# Cheer_Dev_Kit.net
KiCad netlist of a schematic drawn in EAGLE
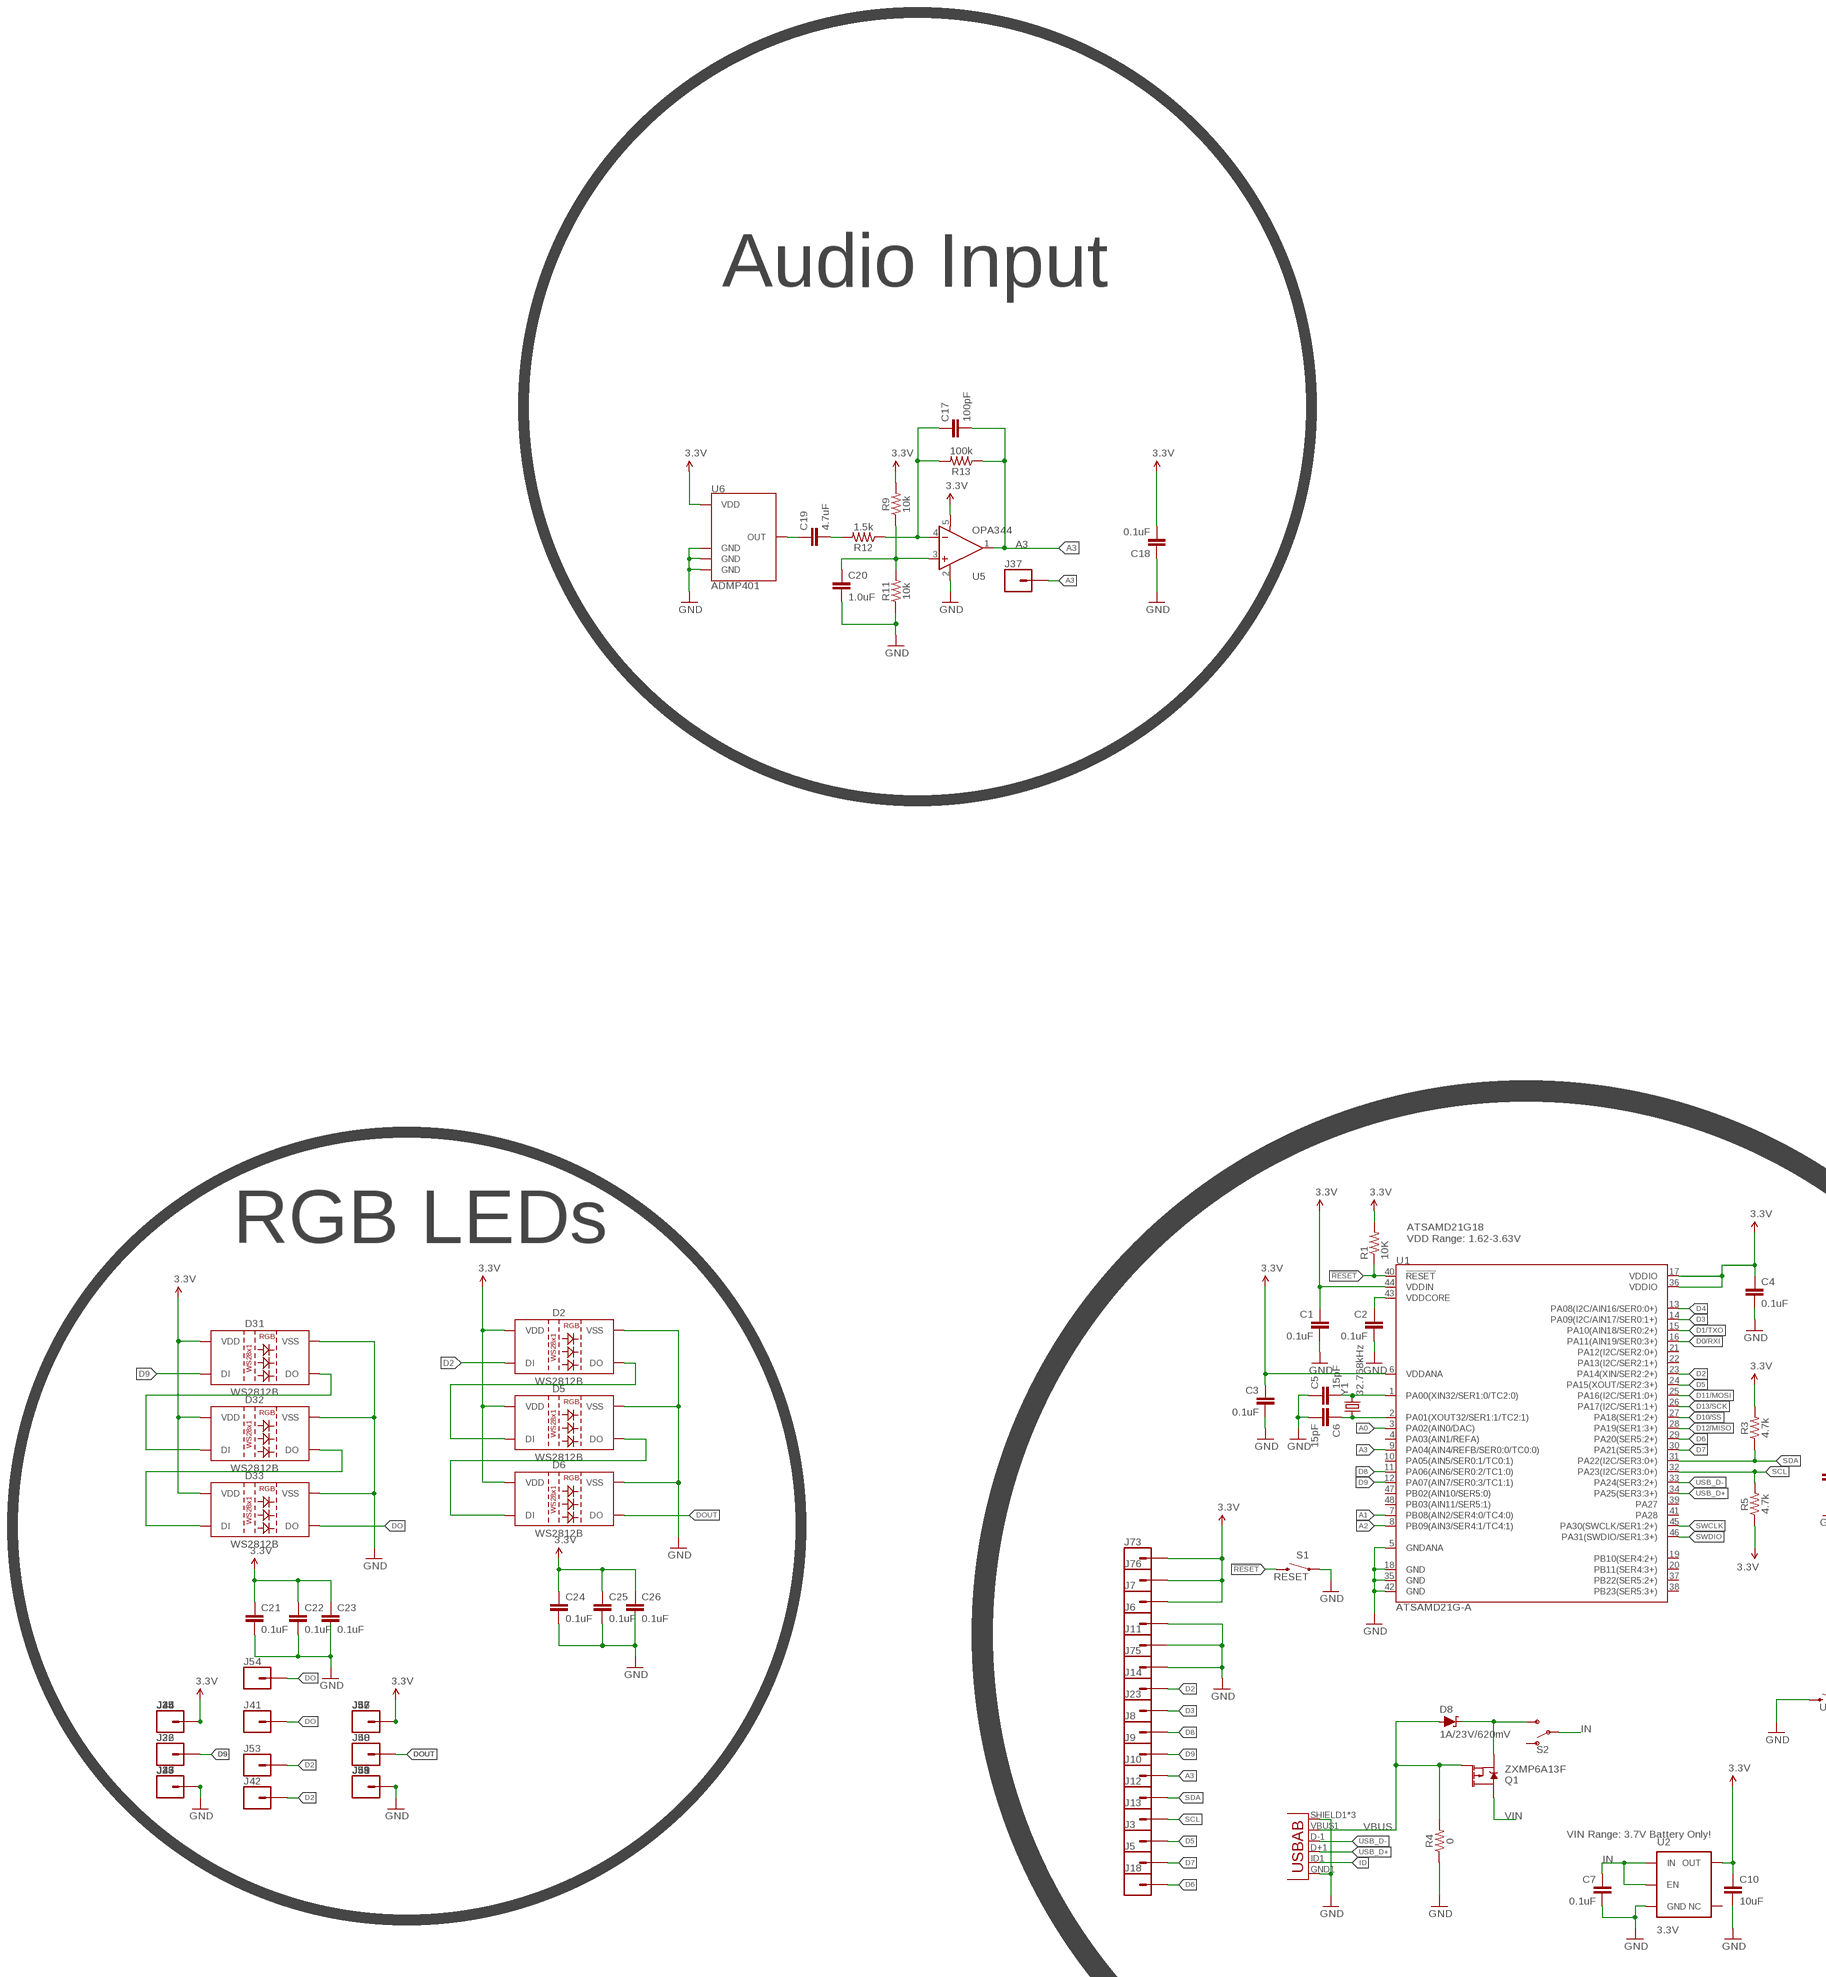
[diagram p0: schematic, sheet 1, part 1 of 3]
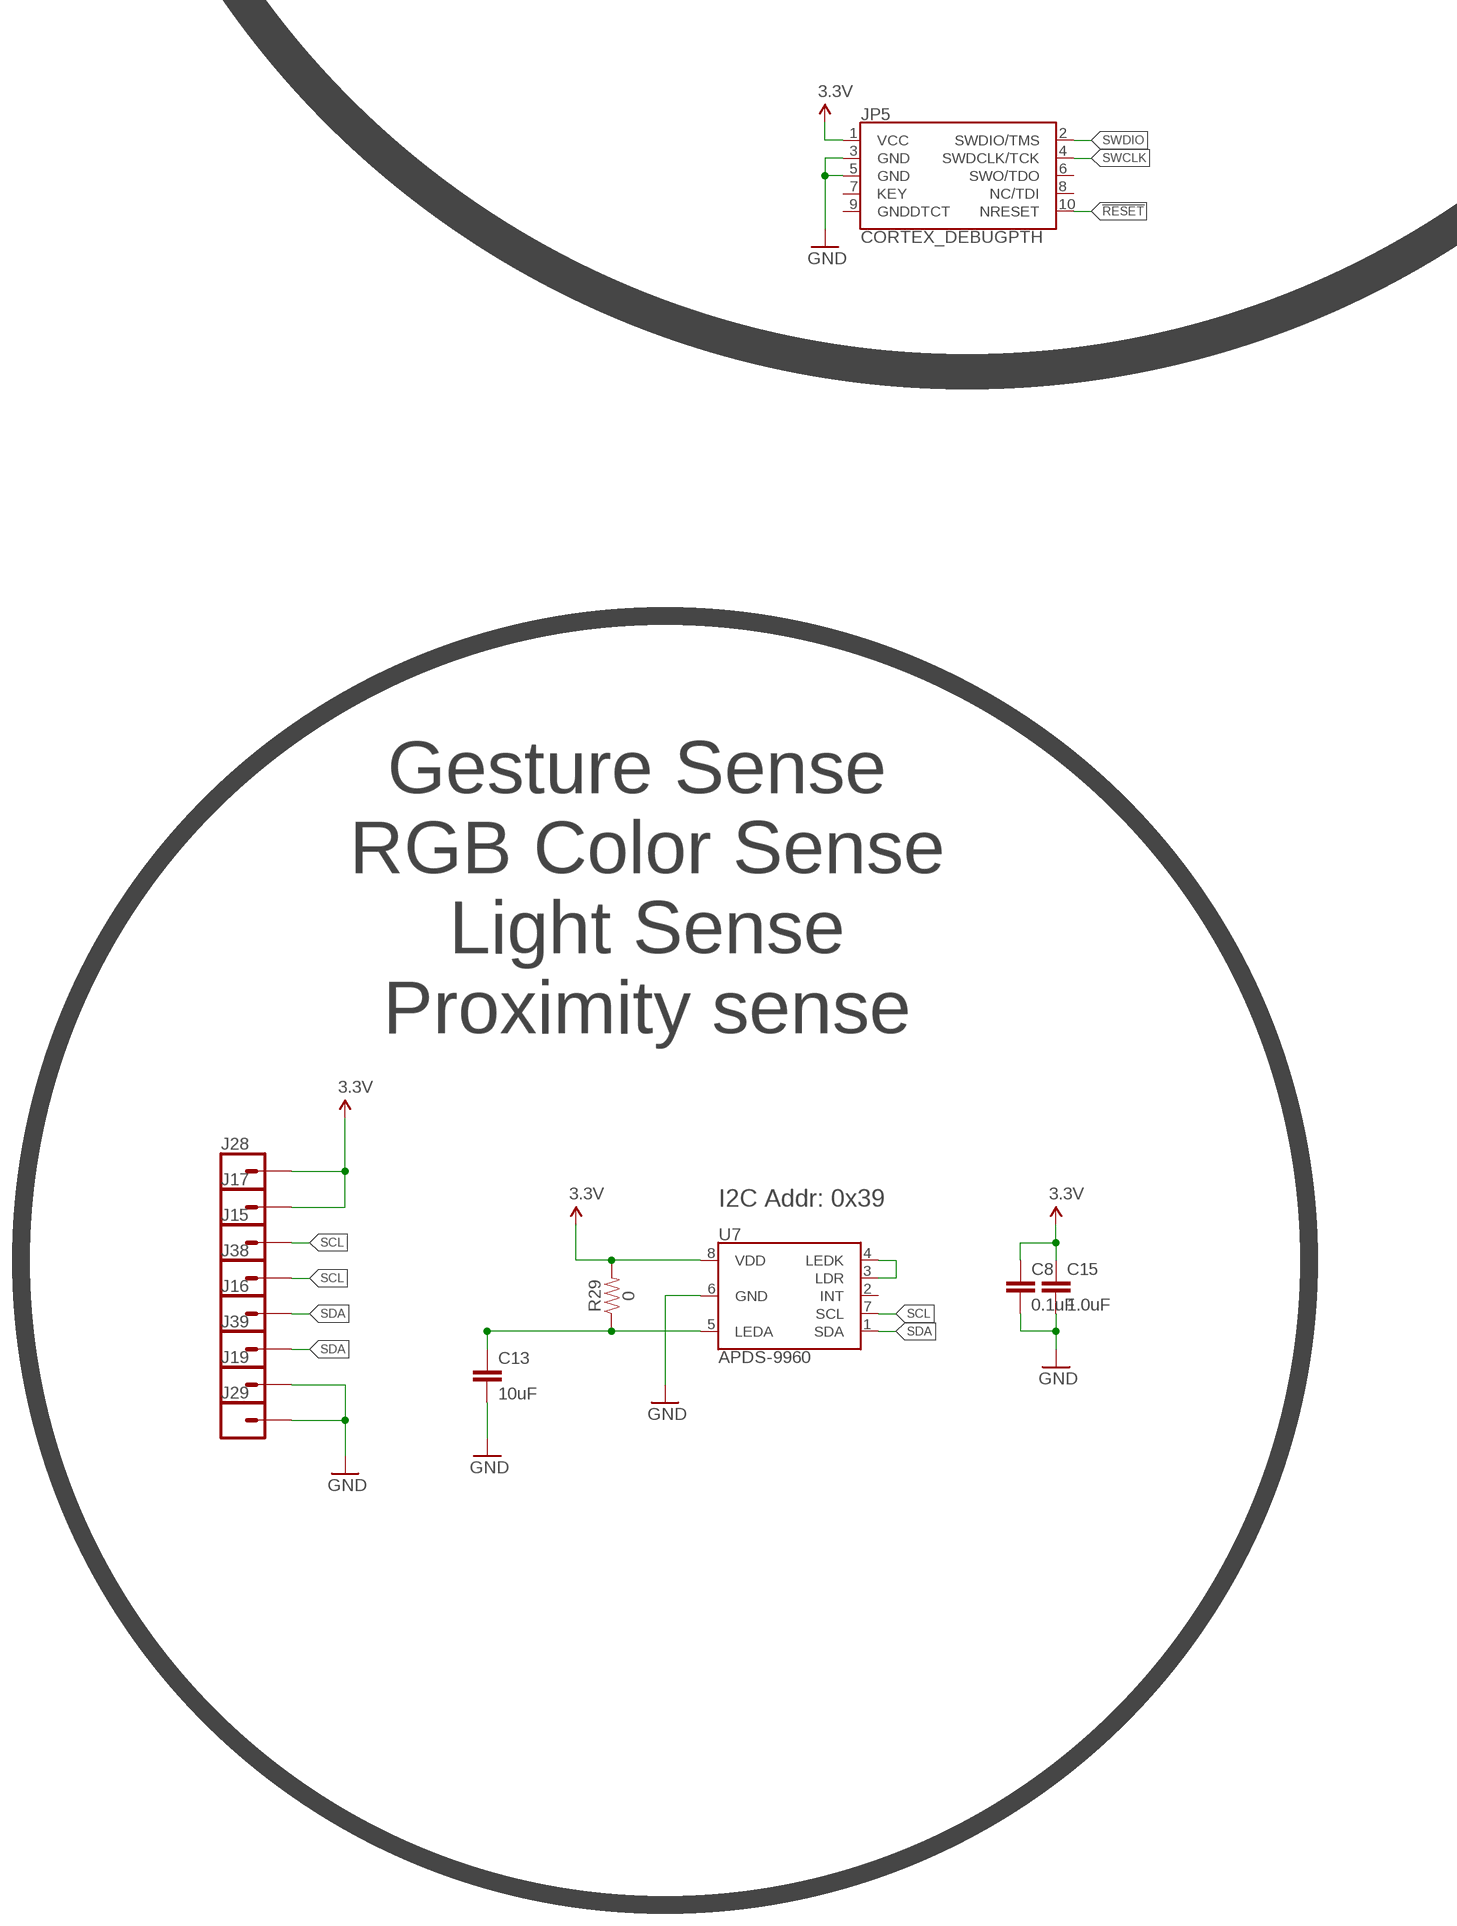
[diagram p1: schematic, sheet 1, part 2 of 3]
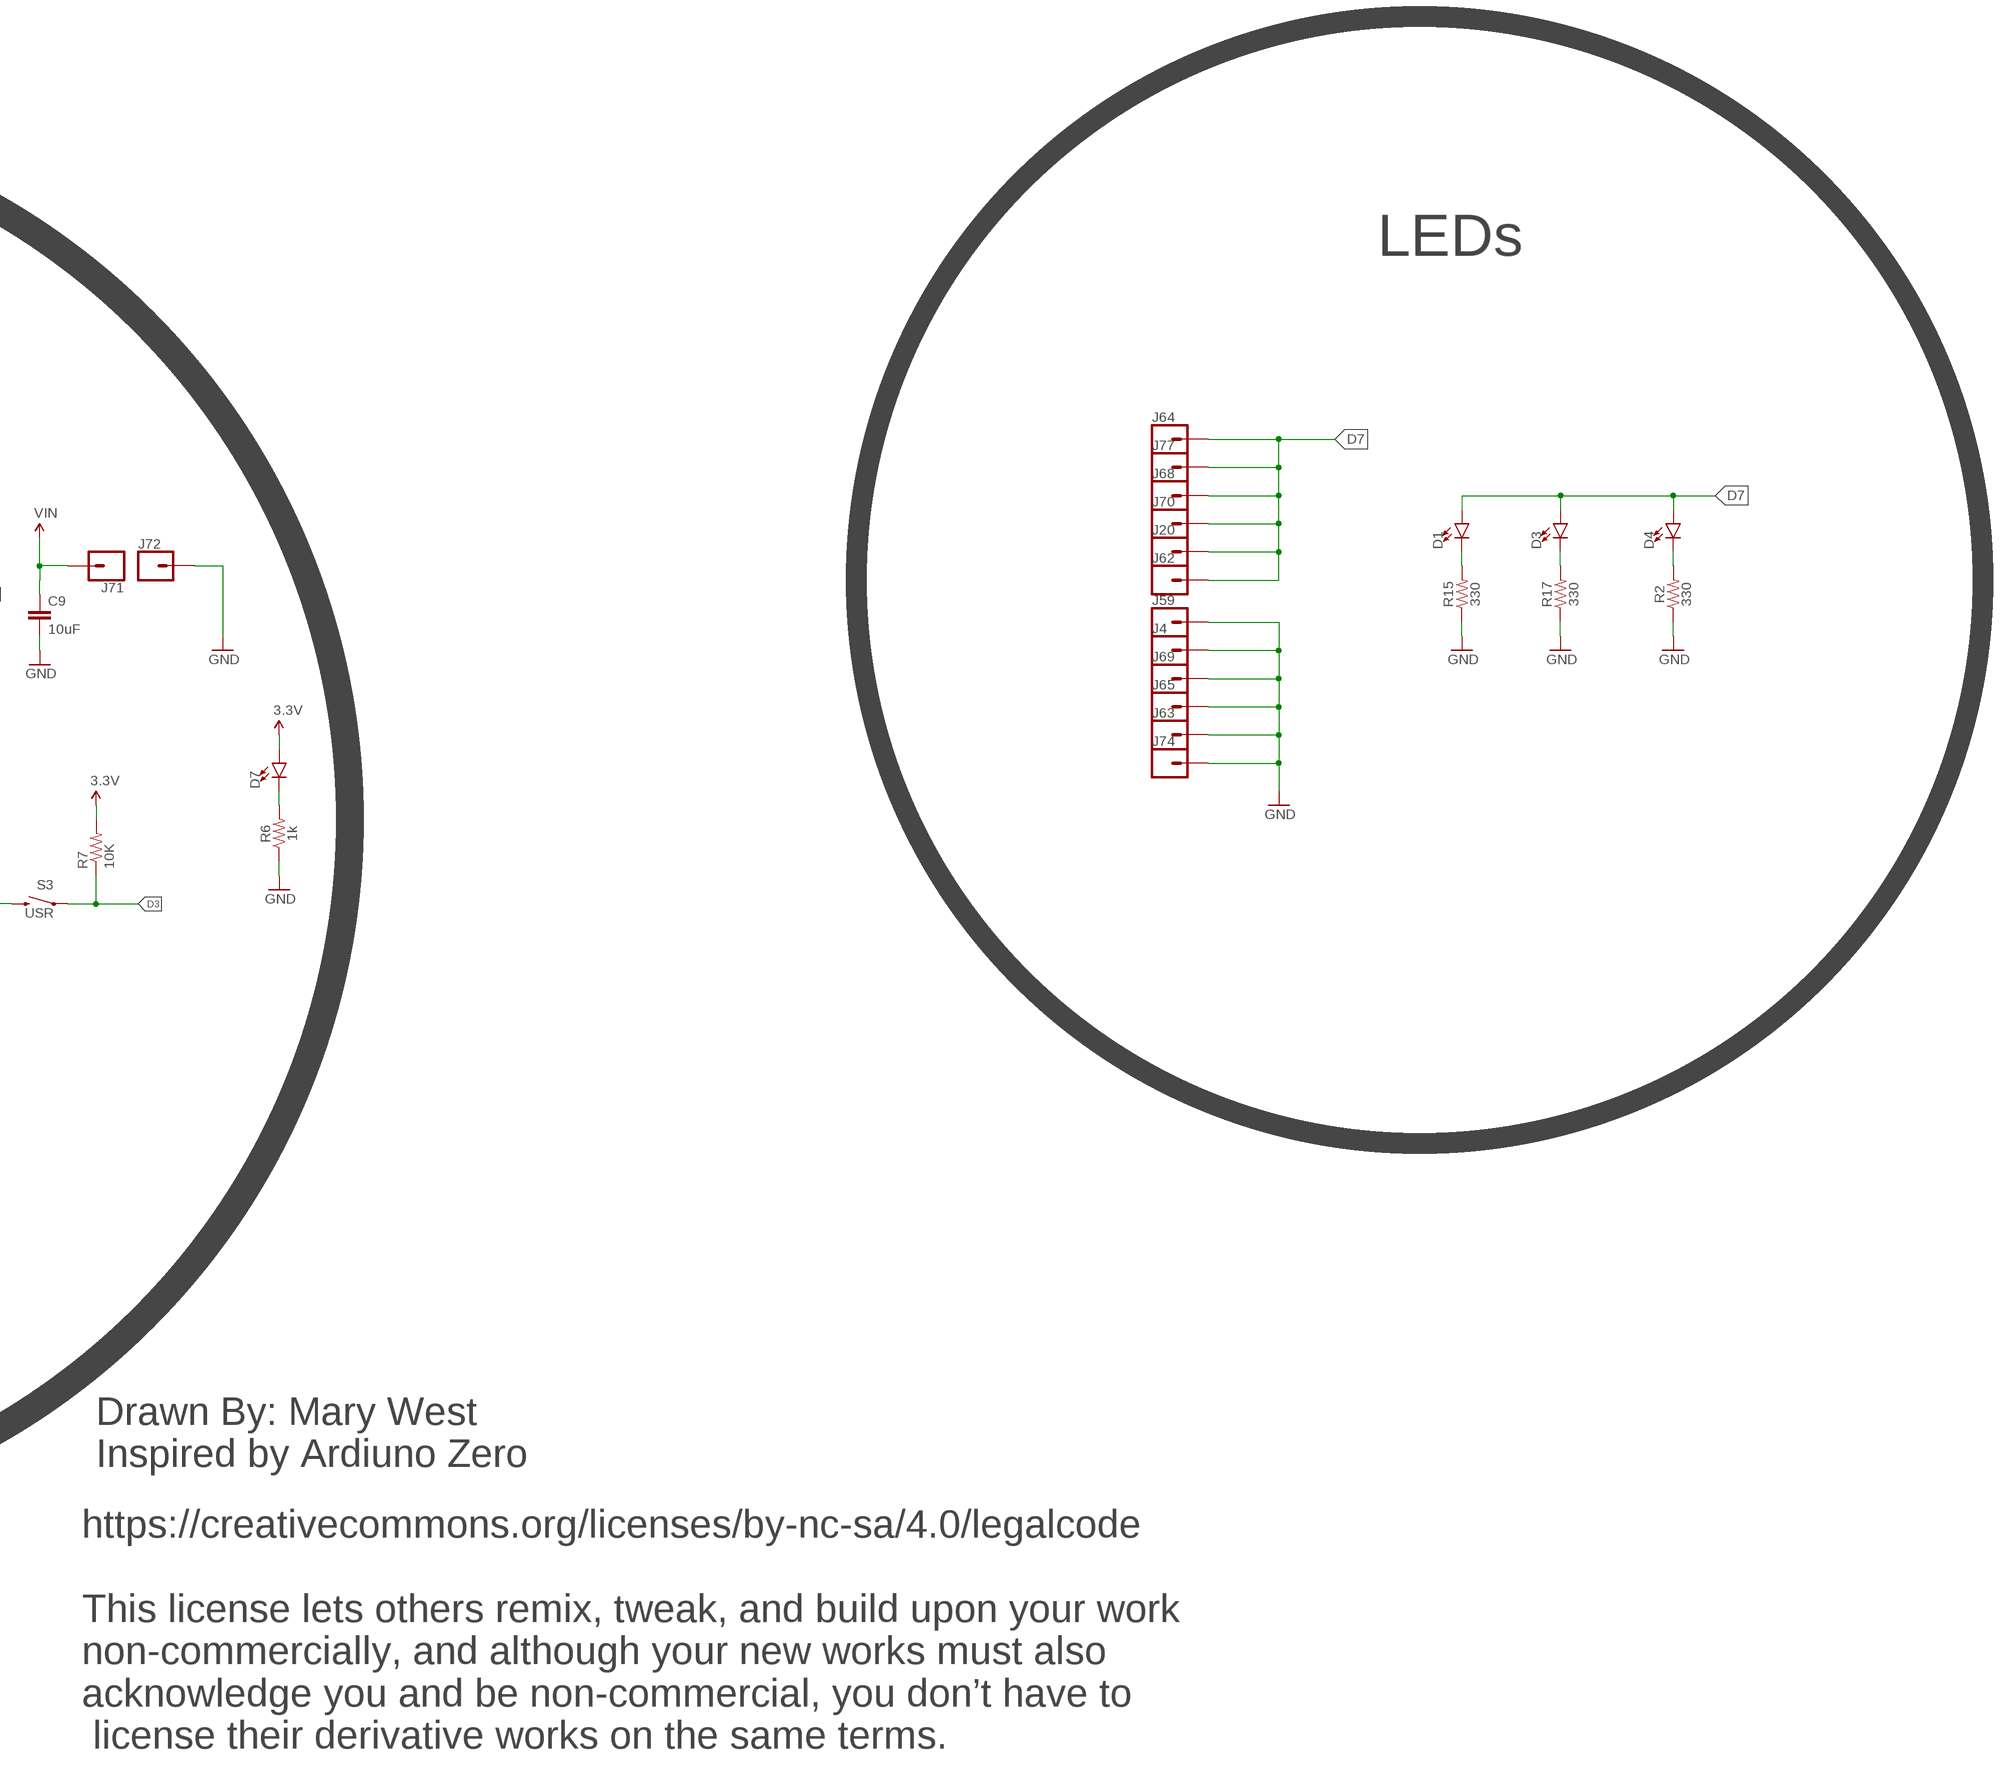
[diagram p2: schematic, sheet 1, part 3 of 3]

(export (version "E")
  (design (tool "Eeschema 10.0.6"))
  (components
    (comp (ref "C1")
      (value "0.1uF")
      (footprint "eagle-import:0603")
      (libsource (lib "eagle-import") (part "0.1UF-0603-25V-(+80/-20%)"))
    )
    (comp (ref "C2")
      (value "0.1uF")
      (footprint "eagle-import:0603")
      (libsource (lib "eagle-import") (part "0.1UF-0603-25V-(+80/-20%)"))
    )
    (comp (ref "C3")
      (value "0.1uF")
      (footprint "eagle-import:0603")
      (libsource (lib "eagle-import") (part "0.1UF-0603-25V-(+80/-20%)"))
    )
    (comp (ref "C4")
      (value "0.1uF")
      (footprint "eagle-import:0603")
      (libsource (lib "eagle-import") (part "0.1UF-0603-25V-(+80/-20%)"))
    )
    (comp (ref "C5")
      (value "15pF")
      (footprint "eagle-import:0603")
      (libsource (lib "eagle-import") (part "15PF-0603-50V-5%"))
    )
    (comp (ref "C6")
      (value "15pF")
      (footprint "eagle-import:0603")
      (libsource (lib "eagle-import") (part "15PF-0603-50V-5%"))
    )
    (comp (ref "C7")
      (value "0.1uF")
      (footprint "eagle-import:0603")
      (libsource (lib "eagle-import") (part "0.1UF-0603-25V-(+80/-20%)"))
    )
    (comp (ref "C8")
      (value "0.1uF")
      (footprint "eagle-import:0603")
      (libsource (lib "eagle-import") (part "0.1UF-0603-25V-(+80/-20%)"))
    )
    (comp (ref "C9")
      (value "10uF")
      (footprint "eagle-import:0603")
      (libsource (lib "eagle-import") (part "SparkFun-Capacitors_510_10UF-0603-6.3V-20%"))
    )
    (comp (ref "C10")
      (value "10uF")
      (footprint "eagle-import:0603")
      (libsource (lib "eagle-import") (part "SparkFun-Capacitors_510_10UF-0603-6.3V-20%"))
    )
    (comp (ref "C13")
      (value "10uF")
      (footprint "eagle-import:0805")
      (libsource (lib "eagle-import") (part "10UF-0805-10V-10%"))
    )
    (comp (ref "C15")
      (value "1.0uF")
      (footprint "eagle-import:0603")
      (libsource (lib "eagle-import") (part "1.0UF-0603-16V-10%"))
    )
    (comp (ref "C17")
      (value "100pF")
      (footprint "eagle-import:0603")
      (libsource (lib "eagle-import") (part "100PF-0603-50V-5%"))
    )
    (comp (ref "C18")
      (value "0.1uF")
      (footprint "eagle-import:0603")
      (libsource (lib "eagle-import") (part "0.1UF-0603-25V-(+80/-20%)"))
    )
    (comp (ref "C19")
      (value "4.7uF")
      (footprint "eagle-import:0603")
      (libsource (lib "eagle-import") (part "4.7UF-0603-6.3V-(10%)"))
    )
    (comp (ref "C20")
      (value "1.0uF")
      (footprint "eagle-import:0603")
      (libsource (lib "eagle-import") (part "1.0UF-0603-16V-10%"))
    )
    (comp (ref "C21")
      (value "0.1uF")
      (footprint "eagle-import:0603")
      (libsource (lib "eagle-import") (part "0.1UF-0603-25V-(+80/-20%)"))
    )
    (comp (ref "C22")
      (value "0.1uF")
      (footprint "eagle-import:0603")
      (libsource (lib "eagle-import") (part "0.1UF-0603-25V-(+80/-20%)"))
    )
    (comp (ref "C23")
      (value "0.1uF")
      (footprint "eagle-import:0603")
      (libsource (lib "eagle-import") (part "0.1UF-0603-25V-(+80/-20%)"))
    )
    (comp (ref "C24")
      (value "0.1uF")
      (footprint "eagle-import:0603")
      (libsource (lib "eagle-import") (part "0.1UF-0603-25V-(+80/-20%)"))
    )
    (comp (ref "C25")
      (value "0.1uF")
      (footprint "eagle-import:0603")
      (libsource (lib "eagle-import") (part "0.1UF-0603-25V-(+80/-20%)"))
    )
    (comp (ref "C26")
      (value "0.1uF")
      (footprint "eagle-import:0603")
      (libsource (lib "eagle-import") (part "0.1UF-0603-25V-(+80/-20%)"))
    )
    (comp (ref "D1")
      (value "LED1206")
      (footprint "eagle-import:LED-1206")
      (libsource (lib "eagle-import") (part "LED1206"))
    )
    (comp (ref "D2")
      (value "WS2812B")
      (footprint "eagle-import:WS2812B")
      (libsource (lib "eagle-import") (part "WS2812B"))
    )
    (comp (ref "D3")
      (value "LED1206")
      (footprint "eagle-import:LED-1206")
      (libsource (lib "eagle-import") (part "LED1206"))
    )
    (comp (ref "D4")
      (value "LED1206")
      (footprint "eagle-import:LED-1206")
      (libsource (lib "eagle-import") (part "LED1206"))
    )
    (comp (ref "D5")
      (value "WS2812B")
      (footprint "eagle-import:WS2812B")
      (libsource (lib "eagle-import") (part "WS2812B"))
    )
    (comp (ref "D6")
      (value "WS2812B")
      (footprint "eagle-import:WS2812B")
      (libsource (lib "eagle-import") (part "WS2812B"))
    )
    (comp (ref "D7")
      (value "LED1206")
      (footprint "eagle-import:LED-1206")
      (libsource (lib "eagle-import") (part "LED1206"))
    )
    (comp (ref "D8")
      (value "1A/23V/620mV")
      (footprint "eagle-import:SOD-323")
      (libsource (lib "eagle-import") (part "DIODE-SCHOTTKY-BAT20J"))
    )
    (comp (ref "D31")
      (value "WS2812B")
      (footprint "eagle-import:WS2812B")
      (libsource (lib "eagle-import") (part "WS2812B"))
    )
    (comp (ref "D32")
      (value "WS2812B")
      (footprint "eagle-import:WS2812B")
      (libsource (lib "eagle-import") (part "WS2812B"))
    )
    (comp (ref "D33")
      (value "WS2812B")
      (footprint "eagle-import:WS2812B")
      (libsource (lib "eagle-import") (part "WS2812B"))
    )
    (comp (ref "J3")
      (value "CONN_01")
      (footprint "eagle-import:1X01")
      (libsource (lib "eagle-import") (part "CONN_01"))
    )
    (comp (ref "J4")
      (value "CONN_01")
      (footprint "eagle-import:1X01")
      (libsource (lib "eagle-import") (part "CONN_01"))
    )
    (comp (ref "J5")
      (value "CONN_01")
      (footprint "eagle-import:1X01")
      (libsource (lib "eagle-import") (part "CONN_01"))
    )
    (comp (ref "J6")
      (value "CONN_01")
      (footprint "eagle-import:1X01")
      (libsource (lib "eagle-import") (part "CONN_01"))
    )
    (comp (ref "J7")
      (value "CONN_01")
      (footprint "eagle-import:1X01")
      (libsource (lib "eagle-import") (part "CONN_01"))
    )
    (comp (ref "J8")
      (value "CONN_01")
      (footprint "eagle-import:1X01")
      (libsource (lib "eagle-import") (part "CONN_01"))
    )
    (comp (ref "J9")
      (value "CONN_01")
      (footprint "eagle-import:1X01")
      (libsource (lib "eagle-import") (part "CONN_01"))
    )
    (comp (ref "J10")
      (value "CONN_01")
      (footprint "eagle-import:1X01")
      (libsource (lib "eagle-import") (part "CONN_01"))
    )
    (comp (ref "J11")
      (value "CONN_01")
      (footprint "eagle-import:1X01")
      (libsource (lib "eagle-import") (part "CONN_01"))
    )
    (comp (ref "J12")
      (value "CONN_01")
      (footprint "eagle-import:1X01")
      (libsource (lib "eagle-import") (part "CONN_01"))
    )
    (comp (ref "J13")
      (value "CONN_01")
      (footprint "eagle-import:1X01")
      (libsource (lib "eagle-import") (part "CONN_01"))
    )
    (comp (ref "J14")
      (value "CONN_01")
      (footprint "eagle-import:1X01")
      (libsource (lib "eagle-import") (part "CONN_01"))
    )
    (comp (ref "J15")
      (value "CONN_01")
      (footprint "eagle-import:1X01")
      (libsource (lib "eagle-import") (part "CONN_01"))
    )
    (comp (ref "J16")
      (value "CONN_01")
      (footprint "eagle-import:1X01")
      (libsource (lib "eagle-import") (part "CONN_01"))
    )
    (comp (ref "J17")
      (value "CONN_01")
      (footprint "eagle-import:1X01")
      (libsource (lib "eagle-import") (part "CONN_01"))
    )
    (comp (ref "J18")
      (value "CONN_01")
      (footprint "eagle-import:1X01")
      (libsource (lib "eagle-import") (part "CONN_01"))
    )
    (comp (ref "J19")
      (value "CONN_01")
      (footprint "eagle-import:1X01")
      (libsource (lib "eagle-import") (part "CONN_01"))
    )
    (comp (ref "J20")
      (value "CONN_01")
      (footprint "eagle-import:1X01")
      (libsource (lib "eagle-import") (part "CONN_01"))
    )
    (comp (ref "J23")
      (value "CONN_01")
      (footprint "eagle-import:1X01")
      (libsource (lib "eagle-import") (part "CONN_01"))
    )
    (comp (ref "J25")
      (value "CONN_01")
      (footprint "eagle-import:1X01")
      (libsource (lib "eagle-import") (part "CONN_01"))
    )
    (comp (ref "J26")
      (value "CONN_01")
      (footprint "eagle-import:1X01")
      (libsource (lib "eagle-import") (part "CONN_01"))
    )
    (comp (ref "J27")
      (value "CONN_01")
      (footprint "eagle-import:1X01")
      (libsource (lib "eagle-import") (part "CONN_01"))
    )
    (comp (ref "J28")
      (value "CONN_01")
      (footprint "eagle-import:1X01")
      (libsource (lib "eagle-import") (part "CONN_01"))
    )
    (comp (ref "J29")
      (value "CONN_01")
      (footprint "eagle-import:1X01")
      (libsource (lib "eagle-import") (part "CONN_01"))
    )
    (comp (ref "J32")
      (value "CONN_01")
      (footprint "eagle-import:1X01")
      (libsource (lib "eagle-import") (part "CONN_01"))
    )
    (comp (ref "J33")
      (value "CONN_01")
      (footprint "eagle-import:1X01")
      (libsource (lib "eagle-import") (part "CONN_01"))
    )
    (comp (ref "J34")
      (value "CONN_01")
      (footprint "eagle-import:1X01")
      (libsource (lib "eagle-import") (part "CONN_01"))
    )
    (comp (ref "J37")
      (value "CONN_01")
      (footprint "eagle-import:1X01")
      (libsource (lib "eagle-import") (part "CONN_01"))
    )
    (comp (ref "J38")
      (value "CONN_01")
      (footprint "eagle-import:1X01")
      (libsource (lib "eagle-import") (part "CONN_01"))
    )
    (comp (ref "J39")
      (value "CONN_01")
      (footprint "eagle-import:1X01")
      (libsource (lib "eagle-import") (part "CONN_01"))
    )
    (comp (ref "J41")
      (value "CONN_01")
      (footprint "eagle-import:1X01")
      (libsource (lib "eagle-import") (part "CONN_01"))
    )
    (comp (ref "J42")
      (value "CONN_01")
      (footprint "eagle-import:1X01")
      (libsource (lib "eagle-import") (part "CONN_01"))
    )
    (comp (ref "J43")
      (value "CONN_01")
      (footprint "eagle-import:1X01")
      (libsource (lib "eagle-import") (part "CONN_01"))
    )
    (comp (ref "J44")
      (value "CONN_01")
      (footprint "eagle-import:1X01")
      (libsource (lib "eagle-import") (part "CONN_01"))
    )
    (comp (ref "J45")
      (value "CONN_01")
      (footprint "eagle-import:1X01")
      (libsource (lib "eagle-import") (part "CONN_01"))
    )
    (comp (ref "J46")
      (value "CONN_01")
      (footprint "eagle-import:1X01")
      (libsource (lib "eagle-import") (part "CONN_01"))
    )
    (comp (ref "J47")
      (value "CONN_01")
      (footprint "eagle-import:1X01")
      (libsource (lib "eagle-import") (part "CONN_01"))
    )
    (comp (ref "J48")
      (value "CONN_01")
      (footprint "eagle-import:1X01")
      (libsource (lib "eagle-import") (part "CONN_01"))
    )
    (comp (ref "J49")
      (value "CONN_01")
      (footprint "eagle-import:1X01")
      (libsource (lib "eagle-import") (part "CONN_01"))
    )
    (comp (ref "J50")
      (value "CONN_01")
      (footprint "eagle-import:1X01")
      (libsource (lib "eagle-import") (part "CONN_01"))
    )
    (comp (ref "J51")
      (value "CONN_01")
      (footprint "eagle-import:1X01")
      (libsource (lib "eagle-import") (part "CONN_01"))
    )
    (comp (ref "J52")
      (value "CONN_01")
      (footprint "eagle-import:1X01")
      (libsource (lib "eagle-import") (part "CONN_01"))
    )
    (comp (ref "J53")
      (value "CONN_01")
      (footprint "eagle-import:1X01")
      (libsource (lib "eagle-import") (part "CONN_01"))
    )
    (comp (ref "J54")
      (value "CONN_01")
      (footprint "eagle-import:1X01")
      (libsource (lib "eagle-import") (part "CONN_01"))
    )
    (comp (ref "J55")
      (value "CONN_01")
      (footprint "eagle-import:1X01")
      (libsource (lib "eagle-import") (part "CONN_01"))
    )
    (comp (ref "J56")
      (value "CONN_01")
      (footprint "eagle-import:1X01")
      (libsource (lib "eagle-import") (part "CONN_01"))
    )
    (comp (ref "J57")
      (value "CONN_01")
      (footprint "eagle-import:1X01")
      (libsource (lib "eagle-import") (part "CONN_01"))
    )
    (comp (ref "J58")
      (value "CONN_01")
      (footprint "eagle-import:1X01")
      (libsource (lib "eagle-import") (part "CONN_01"))
    )
    (comp (ref "J59")
      (value "CONN_01")
      (footprint "eagle-import:1X01")
      (libsource (lib "eagle-import") (part "CONN_01"))
    )
    (comp (ref "J62")
      (value "CONN_01")
      (footprint "eagle-import:1X01")
      (libsource (lib "eagle-import") (part "CONN_01"))
    )
    (comp (ref "J63")
      (value "CONN_01")
      (footprint "eagle-import:1X01")
      (libsource (lib "eagle-import") (part "CONN_01"))
    )
    (comp (ref "J64")
      (value "CONN_01")
      (footprint "eagle-import:1X01")
      (libsource (lib "eagle-import") (part "CONN_01"))
    )
    (comp (ref "J65")
      (value "CONN_01")
      (footprint "eagle-import:1X01")
      (libsource (lib "eagle-import") (part "CONN_01"))
    )
    (comp (ref "J68")
      (value "CONN_01")
      (footprint "eagle-import:1X01")
      (libsource (lib "eagle-import") (part "CONN_01"))
    )
    (comp (ref "J69")
      (value "CONN_01")
      (footprint "eagle-import:1X01")
      (libsource (lib "eagle-import") (part "CONN_01"))
    )
    (comp (ref "J70")
      (value "CONN_01")
      (footprint "eagle-import:1X01")
      (libsource (lib "eagle-import") (part "CONN_01"))
    )
    (comp (ref "J71")
      (value "CONN_01")
      (footprint "eagle-import:1X01")
      (libsource (lib "eagle-import") (part "CONN_01"))
    )
    (comp (ref "J72")
      (value "CONN_01")
      (footprint "eagle-import:1X01")
      (libsource (lib "eagle-import") (part "CONN_01"))
    )
    (comp (ref "J73")
      (value "CONN_01")
      (footprint "eagle-import:1X01")
      (libsource (lib "eagle-import") (part "CONN_01"))
    )
    (comp (ref "J74")
      (value "CONN_01")
      (footprint "eagle-import:1X01")
      (libsource (lib "eagle-import") (part "CONN_01"))
    )
    (comp (ref "J75")
      (value "CONN_01")
      (footprint "eagle-import:1X01")
      (libsource (lib "eagle-import") (part "CONN_01"))
    )
    (comp (ref "J76")
      (value "CONN_01")
      (footprint "eagle-import:1X01")
      (libsource (lib "eagle-import") (part "CONN_01"))
    )
    (comp (ref "J77")
      (value "CONN_01")
      (footprint "eagle-import:1X01")
      (libsource (lib "eagle-import") (part "CONN_01"))
    )
    (comp (ref "JP3")
      (value "USB-ABCONN-11794")
      (footprint "eagle-import:USB-AB-MICRO-SMD_V03")
      (libsource (lib "eagle-import") (part "USB-ABCONN-11794"))
    )
    (comp (ref "JP5")
      (value "CORTEX_DEBUGPTH")
      (footprint "eagle-import:2X5-PTH-1.27MM")
      (libsource (lib "eagle-import") (part "CORTEX_DEBUGPTH"))
    )
    (comp (ref "Q1")
      (value "ZXMP6A13F")
      (footprint "eagle-import:SOT23-3")
      (libsource (lib "eagle-import") (part "MOSFET_PCH-SI2309DS"))
    )
    (comp (ref "R1")
      (value "10K")
      (footprint "eagle-import:0603-RES@1")
      (libsource (lib "eagle-import") (part "10KOHM-1/10W-1%(0603)0603"))
    )
    (comp (ref "R2")
      (value "330")
      (footprint "eagle-import:0603")
      (libsource (lib "eagle-import") (part "330OHM-0603-1/10W-1%"))
    )
    (comp (ref "R3")
      (value "4.7k")
      (footprint "eagle-import:0603")
      (libsource (lib "eagle-import") (part "4.7KOHM-0603-1/10W-1%"))
    )
    (comp (ref "R4")
      (value "0")
      (footprint "eagle-import:0603")
      (libsource (lib "eagle-import") (part "0OHM-0603-1/10W-5%"))
    )
    (comp (ref "R5")
      (value "4.7k")
      (footprint "eagle-import:0603")
      (libsource (lib "eagle-import") (part "4.7KOHM-0603-1/10W-1%"))
    )
    (comp (ref "R6")
      (value "1k")
      (footprint "eagle-import:0603")
      (libsource (lib "eagle-import") (part "330OHM-0603-1/10W-1%"))
    )
    (comp (ref "R7")
      (value "10K")
      (footprint "eagle-import:0603-RES@1")
      (libsource (lib "eagle-import") (part "10KOHM-1/10W-1%(0603)0603"))
    )
    (comp (ref "R9")
      (value "10k")
      (footprint "eagle-import:0603")
      (libsource (lib "eagle-import") (part "10KOHM-0603-1/10W-1%"))
    )
    (comp (ref "R11")
      (value "10k")
      (footprint "eagle-import:0603")
      (libsource (lib "eagle-import") (part "10KOHM-0603-1/10W-1%"))
    )
    (comp (ref "R12")
      (value "1.5k")
      (footprint "eagle-import:0603")
      (libsource (lib "eagle-import") (part "1.5KOHM-0603-1/10W-1%"))
    )
    (comp (ref "R13")
      (value "100k")
      (footprint "eagle-import:0603")
      (libsource (lib "eagle-import") (part "100KOHM-0603-1/10W-1%"))
    )
    (comp (ref "R15")
      (value "330")
      (footprint "eagle-import:0603")
      (libsource (lib "eagle-import") (part "330OHM-0603-1/10W-1%"))
    )
    (comp (ref "R17")
      (value "330")
      (footprint "eagle-import:0603")
      (libsource (lib "eagle-import") (part "330OHM-0603-1/10W-1%"))
    )
    (comp (ref "R29")
      (value "0")
      (footprint "eagle-import:0603")
      (libsource (lib "eagle-import") (part "0OHM-0603-1/10W-5%"))
    )
    (comp (ref "S1")
      (value "RESET")
      (footprint "eagle-import:TACTILE_SWITCH_SMD_4.6X2.8MM")
      (libsource (lib "eagle-import") (part "SWITCH-MOMENTARY-2SMD-4.6X2.8MM"))
    )
    (comp (ref "S2")
      (value "SWITCH-SPDT-SMD-AYZ0202")
      (footprint "eagle-import:SWITCH_DPDT_SMD_AYZ0202")
      (libsource (lib "eagle-import") (part "SWITCH-SPDT-SMD-AYZ0202"))
    )
    (comp (ref "S3")
      (value "USR")
      (footprint "eagle-import:TACTILE_SWITCH_SMD_4.6X2.8MM")
      (libsource (lib "eagle-import") (part "SWITCH-MOMENTARY-2SMD-4.6X2.8MM"))
    )
    (comp (ref "U1")
      (value "ATSAMD21G-A")
      (footprint "eagle-import:TQFP-48")
      (libsource (lib "eagle-import") (part "ATSAMD21G-A"))
    )
    (comp (ref "U2")
      (value "3.3V")
      (footprint "eagle-import:SOT23-5")
      (libsource (lib "eagle-import") (part "V_REG_AP2112K-3.3V"))
    )
    (comp (ref "U5")
      (value "OPA344")
      (footprint "eagle-import:SOT23-5")
      (libsource (lib "eagle-import") (part "OPA344"))
    )
    (comp (ref "U6")
      (value "ADMP401")
      (footprint "eagle-import:ADMP401")
      (libsource (lib "eagle-import") (part "ADMP401"))
    )
    (comp (ref "U7")
      (value "APDS-9960")
      (footprint "eagle-import:APDS-9960")
      (libsource (lib "eagle-import") (part "APDS-9960"))
    )
    (comp (ref "Y1")
      (value "32.768kHz")
      (footprint "eagle-import:CRYSTAL-SMD-3.2X1.5MM")
      (libsource (lib "eagle-import") (part "CRYSTAL3.2X1.5MM"))
    )
  )
  (nets
    (net (code "1") (name "/IN") (class "Default")
      (node (ref "C7") (pin "1") (pinfunction "1_1") (pintype "passive"))
      (node (ref "S2") (pin "2") (pinfunction "P_2") (pintype "passive"))
      (node (ref "U2") (pin "1") (pinfunction "IN_1") (pintype "input"))
      (node (ref "U2") (pin "3") (pinfunction "EN_3") (pintype "input"))
    )
    (net (code "2") (name "/VBUS") (class "Default")
      (node (ref "D8") (pin "A") (pinfunction "A_A") (pintype "passive"))
      (node (ref "JP3") (pin "VBUS1") (pinfunction "VBUS_VBUS1") (pintype "bidirectional"))
      (node (ref "Q1") (pin "1") (pinfunction "G_1") (pintype "bidirectional"))
      (node (ref "R4") (pin "2") (pinfunction "2_2") (pintype "passive"))
    )
    (net (code "3") (name "/~{RESET}") (class "Default")
      (node (ref "JP5") (pin "10") (pinfunction "NRESET_10") (pintype "bidirectional"))
      (node (ref "R1") (pin "1") (pinfunction "1_1") (pintype "passive"))
      (node (ref "S1") (pin "3") (pinfunction "2_3") (pintype "passive"))
      (node (ref "S1") (pin "4") (pinfunction "2_4") (pintype "passive"))
      (node (ref "U1") (pin "40") (pinfunction "~{RESET}_40") (pintype "bidirectional"))
    )
    (net (code "4") (name "3.3V") (class "Default")
      (node (ref "C1") (pin "1") (pinfunction "1_1") (pintype "passive"))
      (node (ref "C10") (pin "1") (pinfunction "1_1") (pintype "passive"))
      (node (ref "C15") (pin "1") (pinfunction "1_1") (pintype "passive"))
      (node (ref "C18") (pin "2") (pinfunction "2_2") (pintype "passive"))
      (node (ref "C21") (pin "1") (pinfunction "1_1") (pintype "passive"))
      (node (ref "C22") (pin "1") (pinfunction "1_1") (pintype "passive"))
      (node (ref "C23") (pin "1") (pinfunction "1_1") (pintype "passive"))
      (node (ref "C24") (pin "1") (pinfunction "1_1") (pintype "passive"))
      (node (ref "C25") (pin "1") (pinfunction "1_1") (pintype "passive"))
      (node (ref "C26") (pin "1") (pinfunction "1_1") (pintype "passive"))
      (node (ref "C3") (pin "1") (pinfunction "1_1") (pintype "passive"))
      (node (ref "C4") (pin "1") (pinfunction "1_1") (pintype "passive"))
      (node (ref "C8") (pin "1") (pinfunction "1_1") (pintype "passive"))
      (node (ref "D2") (pin "1") (pinfunction "VDD_1") (pintype "bidirectional"))
      (node (ref "D31") (pin "1") (pinfunction "VDD_1") (pintype "bidirectional"))
      (node (ref "D32") (pin "1") (pinfunction "VDD_1") (pintype "bidirectional"))
      (node (ref "D33") (pin "1") (pinfunction "VDD_1") (pintype "bidirectional"))
      (node (ref "D5") (pin "1") (pinfunction "VDD_1") (pintype "bidirectional"))
      (node (ref "D6") (pin "1") (pinfunction "VDD_1") (pintype "bidirectional"))
      (node (ref "D7") (pin "A") (pinfunction "A_A") (pintype "passive"))
      (node (ref "J17") (pin "P$1") (pinfunction "1_P$1") (pintype "passive"))
      (node (ref "J25") (pin "P$1") (pinfunction "1_P$1") (pintype "passive"))
      (node (ref "J28") (pin "P$1") (pinfunction "1_P$1") (pintype "passive"))
      (node (ref "J34") (pin "P$1") (pinfunction "1_P$1") (pintype "passive"))
      (node (ref "J44") (pin "P$1") (pinfunction "1_P$1") (pintype "passive"))
      (node (ref "J45") (pin "P$1") (pinfunction "1_P$1") (pintype "passive"))
      (node (ref "J47") (pin "P$1") (pinfunction "1_P$1") (pintype "passive"))
      (node (ref "J52") (pin "P$1") (pinfunction "1_P$1") (pintype "passive"))
      (node (ref "J56") (pin "P$1") (pinfunction "1_P$1") (pintype "passive"))
      (node (ref "J57") (pin "P$1") (pinfunction "1_P$1") (pintype "passive"))
      (node (ref "J7") (pin "P$1") (pinfunction "1_P$1") (pintype "passive"))
      (node (ref "J73") (pin "P$1") (pinfunction "1_P$1") (pintype "passive"))
      (node (ref "J76") (pin "P$1") (pinfunction "1_P$1") (pintype "passive"))
      (node (ref "JP5") (pin "1") (pinfunction "VCC_1") (pintype "bidirectional"))
      (node (ref "R1") (pin "2") (pinfunction "2_2") (pintype "passive"))
      (node (ref "R29") (pin "2") (pinfunction "2_2") (pintype "passive"))
      (node (ref "R3") (pin "2") (pinfunction "2_2") (pintype "passive"))
      (node (ref "R5") (pin "1") (pinfunction "1_1") (pintype "passive"))
      (node (ref "R7") (pin "2") (pinfunction "2_2") (pintype "passive"))
      (node (ref "R9") (pin "2") (pinfunction "2_2") (pintype "passive"))
      (node (ref "U1") (pin "17") (pinfunction "VDDIO_17") (pintype "bidirectional"))
      (node (ref "U1") (pin "36") (pinfunction "VDDIO_36") (pintype "bidirectional"))
      (node (ref "U1") (pin "44") (pinfunction "VDDIN_44") (pintype "bidirectional"))
      (node (ref "U1") (pin "6") (pinfunction "VDDANA_6") (pintype "bidirectional"))
      (node (ref "U2") (pin "5") (pinfunction "OUT_5") (pintype "passive"))
      (node (ref "U5") (pin "5") (pinfunction "V+_5") (pintype "power_in"))
      (node (ref "U6") (pin "5") (pinfunction "VDD_5") (pintype "bidirectional"))
      (node (ref "U7") (pin "8") (pinfunction "VDD_8") (pintype "bidirectional"))
    )
    (net (code "5") (name "A0") (class "Default")
      (node (ref "U1") (pin "3") (pinfunction "PA02(AIN0/DAC)_3") (pintype "bidirectional"))
    )
    (net (code "6") (name "A1") (class "Default")
      (node (ref "U1") (pin "7") (pinfunction "PB08(AIN2/SER4:0/TC4:0)_7") (pintype "bidirectional"))
    )
    (net (code "7") (name "A2") (class "Default")
      (node (ref "U1") (pin "8") (pinfunction "PB09(AIN3/SER4:1/TC4:1)_8") (pintype "bidirectional"))
    )
    (net (code "8") (name "A3") (class "Default")
      (node (ref "C17") (pin "2") (pinfunction "2_2") (pintype "passive"))
      (node (ref "J10") (pin "P$1") (pinfunction "1_P$1") (pintype "passive"))
      (node (ref "J37") (pin "P$1") (pinfunction "1_P$1") (pintype "passive"))
      (node (ref "R13") (pin "1") (pinfunction "1_1") (pintype "passive"))
      (node (ref "U1") (pin "9") (pinfunction "PA04(AIN4/REFB/SER0:0/TC0:0)_9") (pintype "bidirectional"))
      (node (ref "U5") (pin "1") (pinfunction "OUT_1") (pintype "output"))
    )
    (net (code "9") (name "D0{slash}RXI") (class "Default")
      (node (ref "U1") (pin "16") (pinfunction "PA11(AIN19/SER0:3+)_16") (pintype "bidirectional"))
    )
    (net (code "10") (name "D1{slash}TXO") (class "Default")
      (node (ref "U1") (pin "15") (pinfunction "PA10(AIN18/SER0:2+)_15") (pintype "bidirectional"))
    )
    (net (code "11") (name "D2") (class "Default")
      (node (ref "D2") (pin "4") (pinfunction "DI_4") (pintype "bidirectional"))
      (node (ref "J14") (pin "P$1") (pinfunction "1_P$1") (pintype "passive"))
      (node (ref "J42") (pin "P$1") (pinfunction "1_P$1") (pintype "passive"))
      (node (ref "J53") (pin "P$1") (pinfunction "1_P$1") (pintype "passive"))
      (node (ref "U1") (pin "23") (pinfunction "PA14(XIN/SER2:2+)_23") (pintype "bidirectional"))
    )
    (net (code "12") (name "D3") (class "Default")
      (node (ref "J23") (pin "P$1") (pinfunction "1_P$1") (pintype "passive"))
      (node (ref "R7") (pin "1") (pinfunction "1_1") (pintype "passive"))
      (node (ref "S3") (pin "1") (pinfunction "1_1") (pintype "passive"))
      (node (ref "S3") (pin "2") (pinfunction "1_2") (pintype "passive"))
      (node (ref "U1") (pin "14") (pinfunction "PA09(I2C/AIN17/SER0:1+)_14") (pintype "bidirectional"))
    )
    (net (code "13") (name "D4") (class "Default")
      (node (ref "U1") (pin "13") (pinfunction "PA08(I2C/AIN16/SER0:0+)_13") (pintype "bidirectional"))
    )
    (net (code "14") (name "D5") (class "Default")
      (node (ref "J3") (pin "P$1") (pinfunction "1_P$1") (pintype "passive"))
      (node (ref "U1") (pin "24") (pinfunction "PA15(XOUT/SER2:3+)_24") (pintype "bidirectional"))
    )
    (net (code "15") (name "D6") (class "Default")
      (node (ref "J18") (pin "P$1") (pinfunction "1_P$1") (pintype "passive"))
      (node (ref "U1") (pin "29") (pinfunction "PA20(SER5:2+)_29") (pintype "bidirectional"))
    )
    (net (code "16") (name "D7") (class "Default")
      (node (ref "D1") (pin "A") (pinfunction "A_A") (pintype "passive"))
      (node (ref "D3") (pin "A") (pinfunction "A_A") (pintype "passive"))
      (node (ref "D4") (pin "A") (pinfunction "A_A") (pintype "passive"))
      (node (ref "J20") (pin "P$1") (pinfunction "1_P$1") (pintype "passive"))
      (node (ref "J5") (pin "P$1") (pinfunction "1_P$1") (pintype "passive"))
      (node (ref "J62") (pin "P$1") (pinfunction "1_P$1") (pintype "passive"))
      (node (ref "J64") (pin "P$1") (pinfunction "1_P$1") (pintype "passive"))
      (node (ref "J68") (pin "P$1") (pinfunction "1_P$1") (pintype "passive"))
      (node (ref "J70") (pin "P$1") (pinfunction "1_P$1") (pintype "passive"))
      (node (ref "J77") (pin "P$1") (pinfunction "1_P$1") (pintype "passive"))
      (node (ref "U1") (pin "30") (pinfunction "PA21(SER5:3+)_30") (pintype "bidirectional"))
    )
    (net (code "17") (name "D8") (class "Default")
      (node (ref "J8") (pin "P$1") (pinfunction "1_P$1") (pintype "passive"))
      (node (ref "U1") (pin "11") (pinfunction "PA06(AIN6/SER0:2/TC1:0)_11") (pintype "bidirectional"))
    )
    (net (code "18") (name "D9") (class "Default")
      (node (ref "D31") (pin "4") (pinfunction "DI_4") (pintype "bidirectional"))
      (node (ref "J26") (pin "P$1") (pinfunction "1_P$1") (pintype "passive"))
      (node (ref "J32") (pin "P$1") (pinfunction "1_P$1") (pintype "passive"))
      (node (ref "J9") (pin "P$1") (pinfunction "1_P$1") (pintype "passive"))
      (node (ref "U1") (pin "12") (pinfunction "PA07(AIN7/SER0:3/TC1:1)_12") (pintype "bidirectional"))
    )
    (net (code "19") (name "D10{slash}SS") (class "Default")
      (node (ref "U1") (pin "27") (pinfunction "PA18(SER1:2+)_27") (pintype "bidirectional"))
    )
    (net (code "20") (name "D11{slash}MOSI") (class "Default")
      (node (ref "U1") (pin "25") (pinfunction "PA16(I2C/SER1:0+)_25") (pintype "bidirectional"))
    )
    (net (code "21") (name "D12{slash}MISO") (class "Default")
      (node (ref "U1") (pin "28") (pinfunction "PA19(SER1:3+)_28") (pintype "bidirectional"))
    )
    (net (code "22") (name "D13{slash}SCK") (class "Default")
      (node (ref "U1") (pin "26") (pinfunction "PA17(I2C/SER1:1+)_26") (pintype "bidirectional"))
    )
    (net (code "23") (name "DO") (class "Default")
      (node (ref "D33") (pin "2") (pinfunction "DO_2") (pintype "bidirectional"))
      (node (ref "J41") (pin "P$1") (pinfunction "1_P$1") (pintype "passive"))
      (node (ref "J54") (pin "P$1") (pinfunction "1_P$1") (pintype "passive"))
    )
    (net (code "24") (name "DOUT") (class "Default")
      (node (ref "D6") (pin "2") (pinfunction "DO_2") (pintype "bidirectional"))
      (node (ref "J48") (pin "P$1") (pinfunction "1_P$1") (pintype "passive"))
      (node (ref "J50") (pin "P$1") (pinfunction "1_P$1") (pintype "passive"))
    )
    (net (code "25") (name "GND") (class "Default")
      (node (ref "C1") (pin "2") (pinfunction "2_2") (pintype "passive"))
      (node (ref "C10") (pin "2") (pinfunction "2_2") (pintype "passive"))
      (node (ref "C13") (pin "2") (pinfunction "2_2") (pintype "passive"))
      (node (ref "C15") (pin "2") (pinfunction "2_2") (pintype "passive"))
      (node (ref "C18") (pin "1") (pinfunction "1_1") (pintype "passive"))
      (node (ref "C2") (pin "2") (pinfunction "2_2") (pintype "passive"))
      (node (ref "C20") (pin "2") (pinfunction "2_2") (pintype "passive"))
      (node (ref "C21") (pin "2") (pinfunction "2_2") (pintype "passive"))
      (node (ref "C22") (pin "2") (pinfunction "2_2") (pintype "passive"))
      (node (ref "C23") (pin "2") (pinfunction "2_2") (pintype "passive"))
      (node (ref "C24") (pin "2") (pinfunction "2_2") (pintype "passive"))
      (node (ref "C25") (pin "2") (pinfunction "2_2") (pintype "passive"))
      (node (ref "C26") (pin "2") (pinfunction "2_2") (pintype "passive"))
      (node (ref "C3") (pin "2") (pinfunction "2_2") (pintype "passive"))
      (node (ref "C4") (pin "2") (pinfunction "2_2") (pintype "passive"))
      (node (ref "C5") (pin "1") (pinfunction "1_1") (pintype "passive"))
      (node (ref "C6") (pin "2") (pinfunction "2_2") (pintype "passive"))
      (node (ref "C7") (pin "2") (pinfunction "2_2") (pintype "passive"))
      (node (ref "C8") (pin "2") (pinfunction "2_2") (pintype "passive"))
      (node (ref "C9") (pin "2") (pinfunction "2_2") (pintype "passive"))
      (node (ref "D2") (pin "3") (pinfunction "VSS_3") (pintype "bidirectional"))
      (node (ref "D31") (pin "3") (pinfunction "VSS_3") (pintype "bidirectional"))
      (node (ref "D32") (pin "3") (pinfunction "VSS_3") (pintype "bidirectional"))
      (node (ref "D33") (pin "3") (pinfunction "VSS_3") (pintype "bidirectional"))
      (node (ref "D5") (pin "3") (pinfunction "VSS_3") (pintype "bidirectional"))
      (node (ref "D6") (pin "3") (pinfunction "VSS_3") (pintype "bidirectional"))
      (node (ref "J11") (pin "P$1") (pinfunction "1_P$1") (pintype "passive"))
      (node (ref "J19") (pin "P$1") (pinfunction "1_P$1") (pintype "passive"))
      (node (ref "J27") (pin "P$1") (pinfunction "1_P$1") (pintype "passive"))
      (node (ref "J29") (pin "P$1") (pinfunction "1_P$1") (pintype "passive"))
      (node (ref "J33") (pin "P$1") (pinfunction "1_P$1") (pintype "passive"))
      (node (ref "J4") (pin "P$1") (pinfunction "1_P$1") (pintype "passive"))
      (node (ref "J43") (pin "P$1") (pinfunction "1_P$1") (pintype "passive"))
      (node (ref "J46") (pin "P$1") (pinfunction "1_P$1") (pintype "passive"))
      (node (ref "J49") (pin "P$1") (pinfunction "1_P$1") (pintype "passive"))
      (node (ref "J51") (pin "P$1") (pinfunction "1_P$1") (pintype "passive"))
      (node (ref "J55") (pin "P$1") (pinfunction "1_P$1") (pintype "passive"))
      (node (ref "J58") (pin "P$1") (pinfunction "1_P$1") (pintype "passive"))
      (node (ref "J59") (pin "P$1") (pinfunction "1_P$1") (pintype "passive"))
      (node (ref "J6") (pin "P$1") (pinfunction "1_P$1") (pintype "passive"))
      (node (ref "J63") (pin "P$1") (pinfunction "1_P$1") (pintype "passive"))
      (node (ref "J65") (pin "P$1") (pinfunction "1_P$1") (pintype "passive"))
      (node (ref "J69") (pin "P$1") (pinfunction "1_P$1") (pintype "passive"))
      (node (ref "J72") (pin "P$1") (pinfunction "1_P$1") (pintype "passive"))
      (node (ref "J74") (pin "P$1") (pinfunction "1_P$1") (pintype "passive"))
      (node (ref "J75") (pin "P$1") (pinfunction "1_P$1") (pintype "passive"))
      (node (ref "JP3") (pin "GND1") (pinfunction "GND_GND1") (pintype "bidirectional"))
      (node (ref "JP3") (pin "SHIELD1") (pinfunction "SHIELD_SHIELD1") (pintype "bidirectional"))
      (node (ref "JP3") (pin "SHIELD2") (pinfunction "SHIELD_SHIELD2") (pintype "bidirectional"))
      (node (ref "JP3") (pin "SHIELD3") (pinfunction "SHIELD_SHIELD3") (pintype "bidirectional"))
      (node (ref "JP5") (pin "3") (pinfunction "GND_3") (pintype "bidirectional"))
      (node (ref "JP5") (pin "5") (pinfunction "GND_5") (pintype "bidirectional"))
      (node (ref "R11") (pin "1") (pinfunction "1_1") (pintype "passive"))
      (node (ref "R15") (pin "1") (pinfunction "1_1") (pintype "passive"))
      (node (ref "R17") (pin "1") (pinfunction "1_1") (pintype "passive"))
      (node (ref "R2") (pin "1") (pinfunction "1_1") (pintype "passive"))
      (node (ref "R4") (pin "1") (pinfunction "1_1") (pintype "passive"))
      (node (ref "R6") (pin "1") (pinfunction "1_1") (pintype "passive"))
      (node (ref "S1") (pin "1") (pinfunction "1_1") (pintype "passive"))
      (node (ref "S1") (pin "2") (pinfunction "1_2") (pintype "passive"))
      (node (ref "S3") (pin "3") (pinfunction "2_3") (pintype "passive"))
      (node (ref "S3") (pin "4") (pinfunction "2_4") (pintype "passive"))
      (node (ref "U1") (pin "18") (pinfunction "GND_18") (pintype "bidirectional"))
      (node (ref "U1") (pin "35") (pinfunction "GND_35") (pintype "bidirectional"))
      (node (ref "U1") (pin "42") (pinfunction "GND_42") (pintype "bidirectional"))
      (node (ref "U1") (pin "5") (pinfunction "GNDANA_5") (pintype "bidirectional"))
      (node (ref "U2") (pin "2") (pinfunction "GND_2") (pintype "input"))
      (node (ref "U5") (pin "2") (pinfunction "V-_2") (pintype "power_in"))
      (node (ref "U6") (pin "2") (pinfunction "GND_2") (pintype "bidirectional"))
      (node (ref "U6") (pin "4") (pinfunction "GND_4") (pintype "bidirectional"))
      (node (ref "U6") (pin "6") (pinfunction "GND_6") (pintype "bidirectional"))
      (node (ref "U7") (pin "6") (pinfunction "GND_6") (pintype "bidirectional"))
    )
    (net (code "26") (name "ID") (class "Default")
      (node (ref "JP3") (pin "ID1") (pinfunction "USBID_ID1") (pintype "bidirectional"))
    )
    (net (code "27") (name "Net-(C19-Pad2)") (class "Default")
      (node (ref "C19") (pin "2") (pinfunction "2_2") (pintype "passive"))
      (node (ref "R12") (pin "2") (pinfunction "2_2") (pintype "passive"))
    )
    (net (code "28") (name "Net-(D1-PadC)") (class "Default")
      (node (ref "D1") (pin "C") (pinfunction "C_C") (pintype "passive"))
      (node (ref "R15") (pin "2") (pinfunction "2_2") (pintype "passive"))
    )
    (net (code "29") (name "Net-(D2-DO)") (class "Default")
      (node (ref "D2") (pin "2") (pinfunction "DO_2") (pintype "bidirectional"))
      (node (ref "D5") (pin "4") (pinfunction "DI_4") (pintype "bidirectional"))
    )
    (net (code "30") (name "Net-(D3-PadC)") (class "Default")
      (node (ref "D3") (pin "C") (pinfunction "C_C") (pintype "passive"))
      (node (ref "R17") (pin "2") (pinfunction "2_2") (pintype "passive"))
    )
    (net (code "31") (name "Net-(D4-PadC)") (class "Default")
      (node (ref "D4") (pin "C") (pinfunction "C_C") (pintype "passive"))
      (node (ref "R2") (pin "2") (pinfunction "2_2") (pintype "passive"))
    )
    (net (code "32") (name "Net-(D5-DO)") (class "Default")
      (node (ref "D5") (pin "2") (pinfunction "DO_2") (pintype "bidirectional"))
      (node (ref "D6") (pin "4") (pinfunction "DI_4") (pintype "bidirectional"))
    )
    (net (code "33") (name "Net-(D7-PadC)") (class "Default")
      (node (ref "D7") (pin "C") (pinfunction "C_C") (pintype "passive"))
      (node (ref "R6") (pin "2") (pinfunction "2_2") (pintype "passive"))
    )
    (net (code "34") (name "Net-(D31-DO)") (class "Default")
      (node (ref "D31") (pin "2") (pinfunction "DO_2") (pintype "bidirectional"))
      (node (ref "D32") (pin "4") (pinfunction "DI_4") (pintype "bidirectional"))
    )
    (net (code "35") (name "Net-(D32-DO)") (class "Default")
      (node (ref "D32") (pin "2") (pinfunction "DO_2") (pintype "bidirectional"))
      (node (ref "D33") (pin "4") (pinfunction "DI_4") (pintype "bidirectional"))
    )
    (net (code "36") (name "Net-(Q1-S)") (class "Default")
      (node (ref "D8") (pin "C") (pinfunction "C_C") (pintype "passive"))
      (node (ref "Q1") (pin "2") (pinfunction "S_2") (pintype "bidirectional"))
      (node (ref "S2") (pin "3") (pinfunction "S_3") (pintype "passive"))
    )
    (net (code "37") (name "Net-(U1-PA00(XIN32{slash}SER1:0{slash}TC2:0))") (class "Default")
      (node (ref "C5") (pin "2") (pinfunction "2_2") (pintype "passive"))
      (node (ref "U1") (pin "1") (pinfunction "PA00(XIN32/SER1:0/TC2:0)_1") (pintype "bidirectional"))
      (node (ref "Y1") (pin "P$2") (pinfunction "2_P$2") (pintype "passive"))
    )
    (net (code "38") (name "Net-(U1-PA01(XOUT32{slash}SER1:1{slash}TC2:1))") (class "Default")
      (node (ref "C6") (pin "1") (pinfunction "1_1") (pintype "passive"))
      (node (ref "U1") (pin "2") (pinfunction "PA01(XOUT32/SER1:1/TC2:1)_2") (pintype "bidirectional"))
      (node (ref "Y1") (pin "P$1") (pinfunction "1_P$1") (pintype "passive"))
    )
    (net (code "39") (name "Net-(U1-VDDCORE)") (class "Default")
      (node (ref "C2") (pin "1") (pinfunction "1_1") (pintype "passive"))
      (node (ref "U1") (pin "43") (pinfunction "VDDCORE_43") (pintype "bidirectional"))
    )
    (net (code "40") (name "Net-(U5-+IN)") (class "Default")
      (node (ref "C20") (pin "1") (pinfunction "1_1") (pintype "passive"))
      (node (ref "R11") (pin "2") (pinfunction "2_2") (pintype "passive"))
      (node (ref "R9") (pin "1") (pinfunction "1_1") (pintype "passive"))
      (node (ref "U5") (pin "3") (pinfunction "+IN_3") (pintype "input"))
    )
    (net (code "41") (name "Net-(U5--IN)") (class "Default")
      (node (ref "C17") (pin "1") (pinfunction "1_1") (pintype "passive"))
      (node (ref "R12") (pin "1") (pinfunction "1_1") (pintype "passive"))
      (node (ref "R13") (pin "2") (pinfunction "2_2") (pintype "passive"))
      (node (ref "U5") (pin "4") (pinfunction "-IN_4") (pintype "input"))
    )
    (net (code "42") (name "Net-(U6-OUT)") (class "Default")
      (node (ref "C19") (pin "1") (pinfunction "1_1") (pintype "passive"))
      (node (ref "U6") (pin "1") (pinfunction "OUT_1") (pintype "bidirectional"))
    )
    (net (code "43") (name "Net-(U7-LDR)") (class "Default")
      (node (ref "U7") (pin "3") (pinfunction "LDR_3") (pintype "bidirectional"))
      (node (ref "U7") (pin "4") (pinfunction "LEDK_4") (pintype "bidirectional"))
    )
    (net (code "44") (name "Net-(U7-LEDA)") (class "Default")
      (node (ref "C13") (pin "1") (pinfunction "1_1") (pintype "passive"))
      (node (ref "R29") (pin "1") (pinfunction "1_1") (pintype "passive"))
      (node (ref "U7") (pin "5") (pinfunction "LEDA_5") (pintype "bidirectional"))
    )
    (net (code "45") (name "SCL") (class "Default")
      (node (ref "J13") (pin "P$1") (pinfunction "1_P$1") (pintype "passive"))
      (node (ref "J15") (pin "P$1") (pinfunction "1_P$1") (pintype "passive"))
      (node (ref "J38") (pin "P$1") (pinfunction "1_P$1") (pintype "passive"))
      (node (ref "R5") (pin "2") (pinfunction "2_2") (pintype "passive"))
      (node (ref "U1") (pin "32") (pinfunction "PA23(I2C/SER3:0+)_32") (pintype "bidirectional"))
      (node (ref "U7") (pin "7") (pinfunction "SCL_7") (pintype "bidirectional"))
    )
    (net (code "46") (name "SDA") (class "Default")
      (node (ref "J12") (pin "P$1") (pinfunction "1_P$1") (pintype "passive"))
      (node (ref "J16") (pin "P$1") (pinfunction "1_P$1") (pintype "passive"))
      (node (ref "J39") (pin "P$1") (pinfunction "1_P$1") (pintype "passive"))
      (node (ref "R3") (pin "1") (pinfunction "1_1") (pintype "passive"))
      (node (ref "U1") (pin "31") (pinfunction "PA22(I2C/SER3:0+)_31") (pintype "bidirectional"))
      (node (ref "U7") (pin "1") (pinfunction "SDA_1") (pintype "bidirectional"))
    )
    (net (code "47") (name "SWCLK") (class "Default")
      (node (ref "JP5") (pin "4") (pinfunction "SWDCLK/TCK_4") (pintype "bidirectional"))
      (node (ref "U1") (pin "45") (pinfunction "PA30(SWCLK/SER1:2+)_45") (pintype "bidirectional"))
    )
    (net (code "48") (name "SWDIO") (class "Default")
      (node (ref "JP5") (pin "2") (pinfunction "SWDIO/TMS_2") (pintype "bidirectional"))
      (node (ref "U1") (pin "46") (pinfunction "PA31(SWDIO/SER1:3+)_46") (pintype "bidirectional"))
    )
    (net (code "49") (name "USB_D+") (class "Default")
      (node (ref "JP3") (pin "D+1") (pinfunction "D+_D+1") (pintype "bidirectional"))
      (node (ref "U1") (pin "34") (pinfunction "PA25(SER3:3+)_34") (pintype "bidirectional"))
    )
    (net (code "50") (name "USB_D-") (class "Default")
      (node (ref "JP3") (pin "D-1") (pinfunction "D-_D-1") (pintype "bidirectional"))
      (node (ref "U1") (pin "33") (pinfunction "PA24(SER3:2+)_33") (pintype "bidirectional"))
    )
    (net (code "51") (name "VIN") (class "Default")
      (node (ref "C9") (pin "1") (pinfunction "1_1") (pintype "passive"))
      (node (ref "J71") (pin "P$1") (pinfunction "1_P$1") (pintype "passive"))
      (node (ref "Q1") (pin "3") (pinfunction "D_3") (pintype "bidirectional"))
    )
    (net (code "52") (name "unconnected-(JP5-GNDDTCT-Pad9)") (class "Default")
      (node (ref "JP5") (pin "9") (pinfunction "GNDDTCT_9") (pintype "bidirectional"))
    )
    (net (code "53") (name "unconnected-(JP5-KEY-Pad7)") (class "Default")
      (node (ref "JP5") (pin "7") (pinfunction "KEY_7") (pintype "bidirectional"))
    )
    (net (code "54") (name "unconnected-(JP5-NC{slash}TDI-Pad8)") (class "Default")
      (node (ref "JP5") (pin "8") (pinfunction "NC/TDI_8") (pintype "bidirectional"))
    )
    (net (code "55") (name "unconnected-(JP5-SWO{slash}TDO-Pad6)") (class "Default")
      (node (ref "JP5") (pin "6") (pinfunction "SWO/TDO_6") (pintype "bidirectional"))
    )
    (net (code "56") (name "unconnected-(S2-O-Pad1)") (class "Default")
      (node (ref "S2") (pin "1") (pinfunction "O_1") (pintype "passive"))
    )
    (net (code "57") (name "unconnected-(U1-PA03(AIN1{slash}REFA)-Pad4)") (class "Default")
      (node (ref "U1") (pin "4") (pinfunction "PA03(AIN1/REFA)_4") (pintype "bidirectional"))
    )
    (net (code "58") (name "unconnected-(U1-PA05(AIN5{slash}SER0:1{slash}TC0:1)-Pad10)") (class "Default")
      (node (ref "U1") (pin "10") (pinfunction "PA05(AIN5/SER0:1/TC0:1)_10") (pintype "bidirectional"))
    )
    (net (code "59") (name "unconnected-(U1-PA12(I2C{slash}SER2:0+)-Pad21)") (class "Default")
      (node (ref "U1") (pin "21") (pinfunction "PA12(I2C/SER2:0+)_21") (pintype "bidirectional"))
    )
    (net (code "60") (name "unconnected-(U1-PA13(I2C{slash}SER2:1+)-Pad22)") (class "Default")
      (node (ref "U1") (pin "22") (pinfunction "PA13(I2C/SER2:1+)_22") (pintype "bidirectional"))
    )
    (net (code "61") (name "unconnected-(U1-PA27-Pad39)") (class "Default")
      (node (ref "U1") (pin "39") (pinfunction "PA27_39") (pintype "bidirectional"))
    )
    (net (code "62") (name "unconnected-(U1-PA28-Pad41)") (class "Default")
      (node (ref "U1") (pin "41") (pinfunction "PA28_41") (pintype "bidirectional"))
    )
    (net (code "63") (name "unconnected-(U1-PB02(AIN10{slash}SER5:0)-Pad47)") (class "Default")
      (node (ref "U1") (pin "47") (pinfunction "PB02(AIN10/SER5:0)_47") (pintype "bidirectional"))
    )
    (net (code "64") (name "unconnected-(U1-PB03(AIN11{slash}SER5:1)-Pad48)") (class "Default")
      (node (ref "U1") (pin "48") (pinfunction "PB03(AIN11/SER5:1)_48") (pintype "bidirectional"))
    )
    (net (code "65") (name "unconnected-(U1-PB10(SER4:2+)-Pad19)") (class "Default")
      (node (ref "U1") (pin "19") (pinfunction "PB10(SER4:2+)_19") (pintype "bidirectional"))
    )
    (net (code "66") (name "unconnected-(U1-PB11(SER4:3+)-Pad20)") (class "Default")
      (node (ref "U1") (pin "20") (pinfunction "PB11(SER4:3+)_20") (pintype "bidirectional"))
    )
    (net (code "67") (name "unconnected-(U1-PB22(SER5:2+)-Pad37)") (class "Default")
      (node (ref "U1") (pin "37") (pinfunction "PB22(SER5:2+)_37") (pintype "bidirectional"))
    )
    (net (code "68") (name "unconnected-(U1-PB23(SER5:3+)-Pad38)") (class "Default")
      (node (ref "U1") (pin "38") (pinfunction "PB23(SER5:3+)_38") (pintype "bidirectional"))
    )
    (net (code "69") (name "unconnected-(U2-NC-Pad4)") (class "Default")
      (node (ref "U2") (pin "4") (pinfunction "NC_4") (pintype "input"))
    )
    (net (code "70") (name "unconnected-(U7-INT-Pad2)") (class "Default")
      (node (ref "U7") (pin "2") (pinfunction "INT_2") (pintype "bidirectional"))
    )
  )
)
